# AMS_Slave_Inputs.net
KiCad netlist of a schematic drawn in Altium Designer
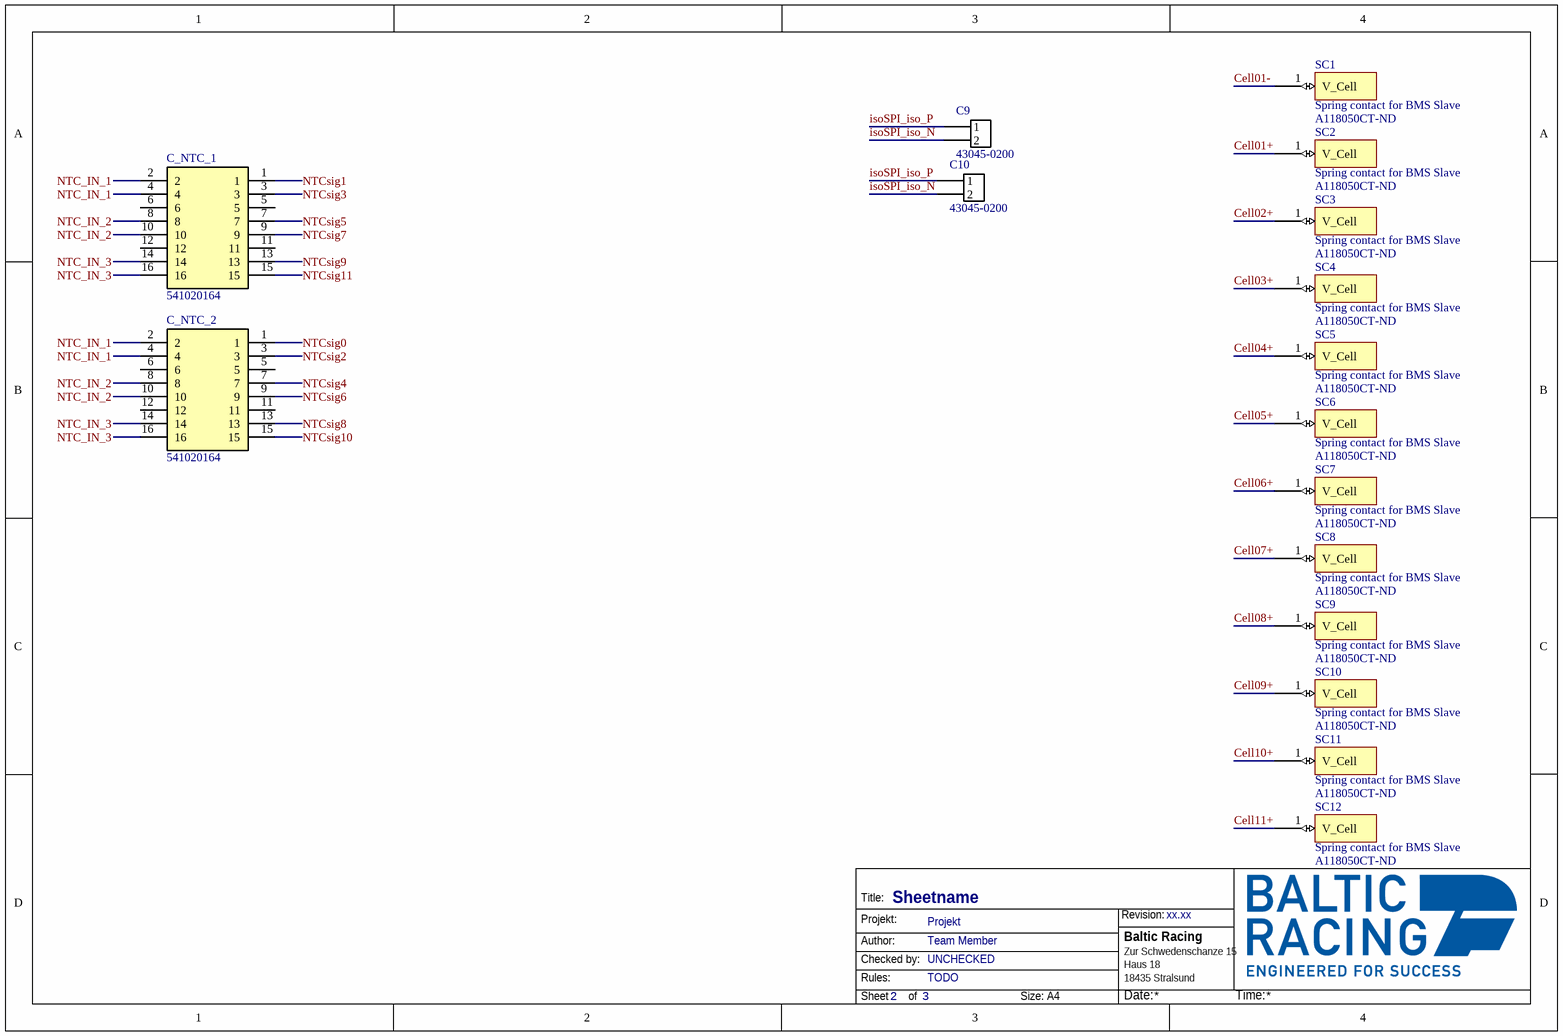
[diagram p0: AMS_Slave_Inputs.SchDoc]

(export (version "E")
  (design (tool "Eeschema 10.0.6"))
  (components
    (comp (ref "C9")
      (value "43045-0200")
      (footprint "43650-0200")
      (description "Molex Micro-Fit 3.0 2-Pin\r\n600V\r\n8.5A")
      (libsource (lib "Standardbauteile") (part "MicroFit3.0 2-Pin"))
    )
    (comp (ref "C10")
      (value "43045-0200")
      (footprint "43650-0200")
      (description "Molex Micro-Fit 3.0 2-Pin\r\n600V\r\n8.5A")
      (libsource (lib "Standardbauteile") (part "MicroFit3.0 2-Pin"))
    )
    (comp (ref "C_NTC_1")
      (value "541020164")
      (footprint "541020164")
      (libsource (lib "libNico") (part "541020164"))
    )
    (comp (ref "C_NTC_2")
      (value "541020164")
      (footprint "541020164")
      (libsource (lib "libNico") (part "541020164"))
    )
    (comp (ref "SC1")
      (value "Spring contact for BMS Slave")
      (footprint "1734300-1 Spring Contact")
      (fields (field (name "SUPPLIER PART NUMBER 1") "A118050CT-ND"))
      (libsource (lib "Integrated_LibraryLukas") (part "1734300-1"))
    )
    (comp (ref "SC2")
      (value "Spring contact for BMS Slave")
      (footprint "1734300-1 Spring Contact")
      (fields (field (name "SUPPLIER PART NUMBER 1") "A118050CT-ND"))
      (libsource (lib "Integrated_LibraryLukas") (part "1734300-1"))
    )
    (comp (ref "SC3")
      (value "Spring contact for BMS Slave")
      (footprint "1734300-1 Spring Contact")
      (fields (field (name "SUPPLIER PART NUMBER 1") "A118050CT-ND"))
      (libsource (lib "Integrated_LibraryLukas") (part "1734300-1"))
    )
    (comp (ref "SC4")
      (value "Spring contact for BMS Slave")
      (footprint "1734300-1 Spring Contact")
      (fields (field (name "SUPPLIER PART NUMBER 1") "A118050CT-ND"))
      (libsource (lib "Integrated_LibraryLukas") (part "1734300-1"))
    )
    (comp (ref "SC5")
      (value "Spring contact for BMS Slave")
      (footprint "1734300-1 Spring Contact")
      (fields (field (name "SUPPLIER PART NUMBER 1") "A118050CT-ND"))
      (libsource (lib "Integrated_LibraryLukas") (part "1734300-1"))
    )
    (comp (ref "SC6")
      (value "Spring contact for BMS Slave")
      (footprint "1734300-1 Spring Contact")
      (fields (field (name "SUPPLIER PART NUMBER 1") "A118050CT-ND"))
      (libsource (lib "Integrated_LibraryLukas") (part "1734300-1"))
    )
    (comp (ref "SC7")
      (value "Spring contact for BMS Slave")
      (footprint "1734300-1 Spring Contact")
      (fields (field (name "SUPPLIER PART NUMBER 1") "A118050CT-ND"))
      (libsource (lib "Integrated_LibraryLukas") (part "1734300-1"))
    )
    (comp (ref "SC8")
      (value "Spring contact for BMS Slave")
      (footprint "1734300-1 Spring Contact")
      (fields (field (name "SUPPLIER PART NUMBER 1") "A118050CT-ND"))
      (libsource (lib "Integrated_LibraryLukas") (part "1734300-1"))
    )
    (comp (ref "SC9")
      (value "Spring contact for BMS Slave")
      (footprint "1734300-1 Spring Contact")
      (fields (field (name "SUPPLIER PART NUMBER 1") "A118050CT-ND"))
      (libsource (lib "Integrated_LibraryLukas") (part "1734300-1"))
    )
    (comp (ref "SC10")
      (value "Spring contact for BMS Slave")
      (footprint "1734300-1 Spring Contact")
      (fields (field (name "SUPPLIER PART NUMBER 1") "A118050CT-ND"))
      (libsource (lib "Integrated_LibraryLukas") (part "1734300-1"))
    )
    (comp (ref "SC11")
      (value "Spring contact for BMS Slave")
      (footprint "1734300-1 Spring Contact")
      (fields (field (name "SUPPLIER PART NUMBER 1") "A118050CT-ND"))
      (libsource (lib "Integrated_LibraryLukas") (part "1734300-1"))
    )
    (comp (ref "SC12")
      (value "Spring contact for BMS Slave")
      (footprint "1734300-1 Spring Contact")
      (fields (field (name "SUPPLIER PART NUMBER 1") "A118050CT-ND"))
      (libsource (lib "Integrated_LibraryLukas") (part "1734300-1"))
    )
  )
  (nets
    (net (code "1") (name "/Cell01+") (class "Default")
      (node (ref "SC2") (pin "1") (pinfunction "V_Cell_1") (pintype "bidirectional"))
    )
    (net (code "2") (name "/Cell01-") (class "Default")
      (node (ref "SC1") (pin "1") (pinfunction "V_Cell_1") (pintype "bidirectional"))
    )
    (net (code "3") (name "/Cell02+") (class "Default")
      (node (ref "SC3") (pin "1") (pinfunction "V_Cell_1") (pintype "bidirectional"))
    )
    (net (code "4") (name "/Cell03+") (class "Default")
      (node (ref "SC4") (pin "1") (pinfunction "V_Cell_1") (pintype "bidirectional"))
    )
    (net (code "5") (name "/Cell04+") (class "Default")
      (node (ref "SC5") (pin "1") (pinfunction "V_Cell_1") (pintype "bidirectional"))
    )
    (net (code "6") (name "/Cell05+") (class "Default")
      (node (ref "SC6") (pin "1") (pinfunction "V_Cell_1") (pintype "bidirectional"))
    )
    (net (code "7") (name "/Cell06+") (class "Default")
      (node (ref "SC7") (pin "1") (pinfunction "V_Cell_1") (pintype "bidirectional"))
    )
    (net (code "8") (name "/Cell07+") (class "Default")
      (node (ref "SC8") (pin "1") (pinfunction "V_Cell_1") (pintype "bidirectional"))
    )
    (net (code "9") (name "/Cell08+") (class "Default")
      (node (ref "SC9") (pin "1") (pinfunction "V_Cell_1") (pintype "bidirectional"))
    )
    (net (code "10") (name "/Cell09+") (class "Default")
      (node (ref "SC10") (pin "1") (pinfunction "V_Cell_1") (pintype "bidirectional"))
    )
    (net (code "11") (name "/Cell10+") (class "Default")
      (node (ref "SC11") (pin "1") (pinfunction "V_Cell_1") (pintype "bidirectional"))
    )
    (net (code "12") (name "/Cell11+") (class "Default")
      (node (ref "SC12") (pin "1") (pinfunction "V_Cell_1") (pintype "bidirectional"))
    )
    (net (code "13") (name "/NTC_IN_1") (class "Default")
      (node (ref "C_NTC_1") (pin "2") (pinfunction "2_2") (pintype "passive"))
      (node (ref "C_NTC_1") (pin "4") (pinfunction "4_4") (pintype "passive"))
      (node (ref "C_NTC_2") (pin "2") (pinfunction "2_2") (pintype "passive"))
      (node (ref "C_NTC_2") (pin "4") (pinfunction "4_4") (pintype "passive"))
    )
    (net (code "14") (name "/NTC_IN_2") (class "Default")
      (node (ref "C_NTC_1") (pin "10") (pinfunction "10_10") (pintype "passive"))
      (node (ref "C_NTC_1") (pin "8") (pinfunction "8_8") (pintype "passive"))
      (node (ref "C_NTC_2") (pin "10") (pinfunction "10_10") (pintype "passive"))
      (node (ref "C_NTC_2") (pin "8") (pinfunction "8_8") (pintype "passive"))
    )
    (net (code "15") (name "/NTC_IN_3") (class "Default")
      (node (ref "C_NTC_1") (pin "14") (pinfunction "14_14") (pintype "passive"))
      (node (ref "C_NTC_1") (pin "16") (pinfunction "16_16") (pintype "passive"))
      (node (ref "C_NTC_2") (pin "14") (pinfunction "14_14") (pintype "passive"))
      (node (ref "C_NTC_2") (pin "16") (pinfunction "16_16") (pintype "passive"))
    )
    (net (code "16") (name "/NTCsig0") (class "Default")
      (node (ref "C_NTC_2") (pin "1") (pinfunction "1_1") (pintype "passive"))
    )
    (net (code "17") (name "/NTCsig1") (class "Default")
      (node (ref "C_NTC_1") (pin "1") (pinfunction "1_1") (pintype "passive"))
    )
    (net (code "18") (name "/NTCsig2") (class "Default")
      (node (ref "C_NTC_2") (pin "3") (pinfunction "3_3") (pintype "passive"))
    )
    (net (code "19") (name "/NTCsig3") (class "Default")
      (node (ref "C_NTC_1") (pin "3") (pinfunction "3_3") (pintype "passive"))
    )
    (net (code "20") (name "/NTCsig4") (class "Default")
      (node (ref "C_NTC_2") (pin "7") (pinfunction "7_7") (pintype "passive"))
    )
    (net (code "21") (name "/NTCsig5") (class "Default")
      (node (ref "C_NTC_1") (pin "7") (pinfunction "7_7") (pintype "passive"))
    )
    (net (code "22") (name "/NTCsig6") (class "Default")
      (node (ref "C_NTC_2") (pin "9") (pinfunction "9_9") (pintype "passive"))
    )
    (net (code "23") (name "/NTCsig7") (class "Default")
      (node (ref "C_NTC_1") (pin "9") (pinfunction "9_9") (pintype "passive"))
    )
    (net (code "24") (name "/NTCsig8") (class "Default")
      (node (ref "C_NTC_2") (pin "13") (pinfunction "13_13") (pintype "passive"))
    )
    (net (code "25") (name "/NTCsig9") (class "Default")
      (node (ref "C_NTC_1") (pin "13") (pinfunction "13_13") (pintype "passive"))
    )
    (net (code "26") (name "/NTCsig10") (class "Default")
      (node (ref "C_NTC_2") (pin "15") (pinfunction "15_15") (pintype "passive"))
    )
    (net (code "27") (name "/NTCsig11") (class "Default")
      (node (ref "C_NTC_1") (pin "15") (pinfunction "15_15") (pintype "passive"))
    )
    (net (code "28") (name "/isoSPI_iso_N") (class "Default")
      (node (ref "C10") (pin "2") (pinfunction "2_2") (pintype "passive"))
      (node (ref "C9") (pin "2") (pinfunction "2_2") (pintype "passive"))
    )
    (net (code "29") (name "/isoSPI_iso_P") (class "Default")
      (node (ref "C10") (pin "1") (pinfunction "1_1") (pintype "passive"))
      (node (ref "C9") (pin "1") (pinfunction "1_1") (pintype "passive"))
    )
    (net (code "30") (name "unconnected-(C_NTC_1-Pad5)") (class "Default")
      (node (ref "C_NTC_1") (pin "5") (pinfunction "5_5") (pintype "passive"))
    )
    (net (code "31") (name "unconnected-(C_NTC_1-Pad6)") (class "Default")
      (node (ref "C_NTC_1") (pin "6") (pinfunction "6_6") (pintype "passive"))
    )
    (net (code "32") (name "unconnected-(C_NTC_1-Pad11)") (class "Default")
      (node (ref "C_NTC_1") (pin "11") (pinfunction "11_11") (pintype "passive"))
    )
    (net (code "33") (name "unconnected-(C_NTC_1-Pad12)") (class "Default")
      (node (ref "C_NTC_1") (pin "12") (pinfunction "12_12") (pintype "passive"))
    )
    (net (code "34") (name "unconnected-(C_NTC_2-Pad5)") (class "Default")
      (node (ref "C_NTC_2") (pin "5") (pinfunction "5_5") (pintype "passive"))
    )
    (net (code "35") (name "unconnected-(C_NTC_2-Pad6)") (class "Default")
      (node (ref "C_NTC_2") (pin "6") (pinfunction "6_6") (pintype "passive"))
    )
    (net (code "36") (name "unconnected-(C_NTC_2-Pad11)") (class "Default")
      (node (ref "C_NTC_2") (pin "11") (pinfunction "11_11") (pintype "passive"))
    )
    (net (code "37") (name "unconnected-(C_NTC_2-Pad12)") (class "Default")
      (node (ref "C_NTC_2") (pin "12") (pinfunction "12_12") (pintype "passive"))
    )
  )
)
